# OSCILADOR-LOCAL.net
KiCad netlist of a schematic drawn in Altium Designer
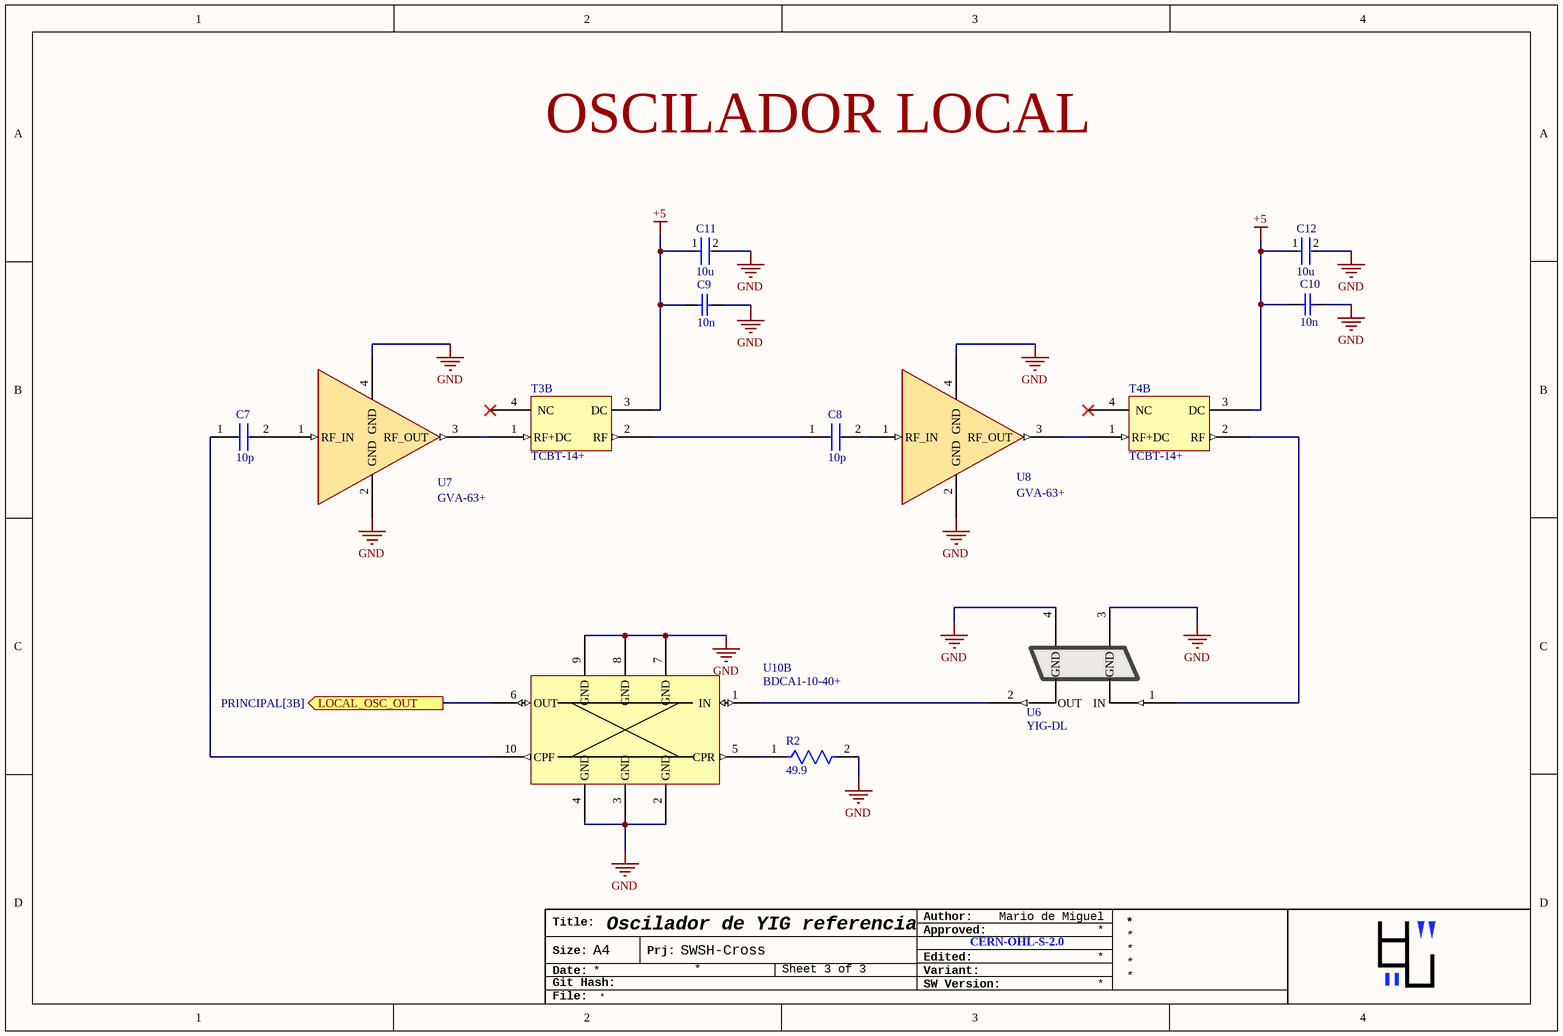
[diagram p0: OSCILADOR-LOCAL.SchDoc]

(export (version "E")
  (design (tool "Eeschema 10.0.6"))
  (components
    (comp (ref "C7")
      (value "10p")
      (footprint "GRM1555C2A100FA01D")
      (libsource (lib "GRM1555C2A100FA01D") (part "GRM1555C2A100FA01D"))
    )
    (comp (ref "C8")
      (value "10p")
      (footprint "GRM1555C2A100FA01D")
      (libsource (lib "GRM1555C2A100FA01D") (part "GRM1555C2A100FA01D"))
    )
    (comp (ref "C9")
      (value "10n")
      (footprint "CAPC1608X90X35LL10T15")
      (fields (field (name "PART NUMBER") "GCM188R71H103KA37D") (field (name "MANUFACTURER") "Murata"))
      (libsource (lib "Altium Content Vault") (part "CAP"))
    )
    (comp (ref "C10")
      (value "10n")
      (footprint "CAPC1608X90X35LL10T15")
      (fields (field (name "PART NUMBER") "GCM188R71H103KA37D") (field (name "MANUFACTURER") "Murata"))
      (libsource (lib "Altium Content Vault") (part "CAP"))
    )
    (comp (ref "C11")
      (value "10u")
      (footprint "FP-GRM21B-0_1-MFG")
      (description "Chip Multilayer Ceramic Capacitors for General Purpose, 0805, 10uF, X5R, 15%, 10%, 16V")
      (fields (field (name "TOLERANCE") "10%") (field (name "VOLTAGE") "16V"))
      (libsource (lib "Altium Content Vault") (part "b4654b650e69147ec39a6b967a45e02"))
    )
    (comp (ref "C12")
      (value "10u")
      (footprint "FP-GRM21B-0_1-MFG")
      (description "Chip Multilayer Ceramic Capacitors for General Purpose, 0805, 10uF, X5R, 15%, 10%, 16V")
      (fields (field (name "TOLERANCE") "10%") (field (name "VOLTAGE") "16V"))
      (libsource (lib "Altium Content Vault") (part "b4654b650e69147ec39a6b967a45e02"))
    )
    (comp (ref "R2")
      (value "49.9")
      (footprint "FP-RNCP0603-IPC_C")
      (description "49.9Ω ±1% 0.125W 0603 High Power Anti-Sulfur Thin Film Chip Resistor")
      (fields (field (name "TOLERANCE") "1%"))
      (libsource (lib "Altium Content Vault") (part "1029c3af85768c4190bb7ad29bc67b5"))
    )
    (comp (ref "T3")
      (value "TCBT-14+")
      (footprint "PL321-GU1414-TCBT-14+")
      (libsource (lib "TCBT-14+") (part "TCBT-14+"))
    )
    (comp (ref "T4")
      (value "TCBT-14+")
      (footprint "PL321-GU1414-TCBT-14+")
      (libsource (lib "TCBT-14+") (part "TCBT-14+"))
    )
    (comp (ref "U6") (value "YIG-DL") (footprint "YIG_DL_5mm-C") (libsource (lib "YIG-DL") (part "YIG-DL")))
    (comp (ref "U7")
      (value "GVA-63+")
      (footprint "DF782-GVA-63+")
      (libsource (lib "GVA-63+") (part "GVA-63+"))
    )
    (comp (ref "U8")
      (value "GVA-63+")
      (footprint "DF782-GVA-63+")
      (libsource (lib "GVA-63+") (part "GVA-63+"))
    )
    (comp (ref "U10")
      (value "BDCA1-10-40+")
      (footprint "PL400-DZ944-BDCA1-10-40")
      (libsource (lib "BDCA1-10-40+") (part "BDCA1-10-40+"))
    )
  )
  (nets
    (net (code "1") (name "+5") (class "Default")
      (node (ref "C10") (pin "2") (pinfunction "2_2") (pintype "passive"))
      (node (ref "C11") (pin "1") (pinfunction "1_1") (pintype "passive"))
      (node (ref "C12") (pin "1") (pinfunction "1_1") (pintype "passive"))
      (node (ref "C9") (pin "2") (pinfunction "2_2") (pintype "passive"))
      (node (ref "T3") (pin "3") (pinfunction "DC_3") (pintype "power_in"))
      (node (ref "T4") (pin "3") (pinfunction "DC_3") (pintype "power_in"))
    )
    (net (code "2") (name "/LOCAL_OSC_OUT") (class "Default")
      (node (ref "U10") (pin "6") (pinfunction "OUT_6") (pintype "bidirectional"))
    )
    (net (code "3") (name "GND") (class "Default")
      (node (ref "C10") (pin "1") (pinfunction "1_1") (pintype "passive"))
      (node (ref "C11") (pin "2") (pinfunction "2_2") (pintype "passive"))
      (node (ref "C12") (pin "2") (pinfunction "2_2") (pintype "passive"))
      (node (ref "C9") (pin "1") (pinfunction "1_1") (pintype "passive"))
      (node (ref "R2") (pin "2") (pinfunction "2_2") (pintype "passive"))
      (node (ref "U10") (pin "2") (pinfunction "GND_2") (pintype "power_in"))
      (node (ref "U10") (pin "3") (pinfunction "GND_3") (pintype "power_in"))
      (node (ref "U10") (pin "4") (pinfunction "GND_4") (pintype "power_in"))
      (node (ref "U10") (pin "7") (pinfunction "GND_7") (pintype "power_in"))
      (node (ref "U10") (pin "8") (pinfunction "GND_8") (pintype "power_in"))
      (node (ref "U10") (pin "9") (pinfunction "GND_9") (pintype "power_in"))
      (node (ref "U6") (pin "3") (pinfunction "GND_3") (pintype "power_in"))
      (node (ref "U6") (pin "4") (pinfunction "GND_4") (pintype "power_in"))
      (node (ref "U7") (pin "2") (pinfunction "GND_2") (pintype "power_in"))
      (node (ref "U7") (pin "4") (pinfunction "GND_4") (pintype "power_in"))
      (node (ref "U8") (pin "2") (pinfunction "GND_2") (pintype "power_in"))
      (node (ref "U8") (pin "4") (pinfunction "GND_4") (pintype "power_in"))
    )
    (net (code "4") (name "Net-(T3B-RF)") (class "Default")
      (node (ref "C8") (pin "1") (pinfunction "1_1") (pintype "passive"))
      (node (ref "T3") (pin "2") (pinfunction "RF_2") (pintype "output"))
    )
    (net (code "5") (name "Net-(T3B-RF+DC)") (class "Default")
      (node (ref "T3") (pin "1") (pinfunction "RF+DC_1") (pintype "input"))
      (node (ref "U7") (pin "3") (pinfunction "RF_OUT_3") (pintype "output"))
    )
    (net (code "6") (name "Net-(T4B-RF)") (class "Default")
      (node (ref "T4") (pin "2") (pinfunction "RF_2") (pintype "output"))
      (node (ref "U6") (pin "1") (pinfunction "IN_1") (pintype "input"))
    )
    (net (code "7") (name "Net-(T4B-RF+DC)") (class "Default")
      (node (ref "T4") (pin "1") (pinfunction "RF+DC_1") (pintype "input"))
      (node (ref "U8") (pin "3") (pinfunction "RF_OUT_3") (pintype "output"))
    )
    (net (code "8") (name "Net-(U7-RF_IN)") (class "Default")
      (node (ref "C7") (pin "2") (pinfunction "2_2") (pintype "passive"))
      (node (ref "U7") (pin "1") (pinfunction "RF_IN_1") (pintype "input"))
    )
    (net (code "9") (name "Net-(U8-RF_IN)") (class "Default")
      (node (ref "C8") (pin "2") (pinfunction "2_2") (pintype "passive"))
      (node (ref "U8") (pin "1") (pinfunction "RF_IN_1") (pintype "input"))
    )
    (net (code "10") (name "Net-(U10B-CPF)") (class "Default")
      (node (ref "C7") (pin "1") (pinfunction "1_1") (pintype "passive"))
      (node (ref "U10") (pin "10") (pinfunction "CPF_10") (pintype "output"))
    )
    (net (code "11") (name "Net-(U10B-CPR)") (class "Default")
      (node (ref "R2") (pin "1") (pinfunction "1_1") (pintype "passive"))
      (node (ref "U10") (pin "5") (pinfunction "CPR_5") (pintype "output"))
    )
    (net (code "12") (name "Net-(U10B-IN)") (class "Default")
      (node (ref "U10") (pin "1") (pinfunction "IN_1") (pintype "bidirectional"))
      (node (ref "U6") (pin "2") (pinfunction "OUT_2") (pintype "output"))
    )
    (net (code "13") (name "unconnected-(T3B-NC-Pad4)") (class "Default")
      (node (ref "T3") (pin "4") (pinfunction "NC_4") (pintype "passive+no_connect"))
    )
    (net (code "14") (name "unconnected-(T4B-NC-Pad4)") (class "Default")
      (node (ref "T4") (pin "4") (pinfunction "NC_4") (pintype "passive+no_connect"))
    )
  )
)
